# Power.net
KiCad netlist of a schematic drawn in Altium Designer
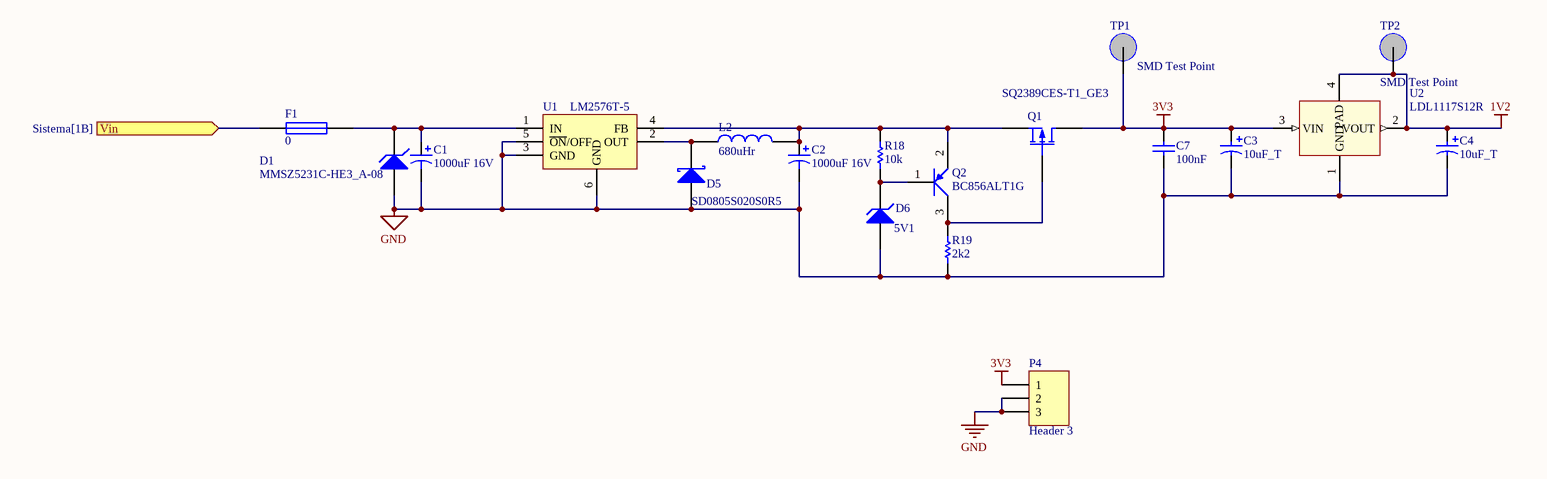
[diagram p0: Power.SchDoc]

(export (version "E")
  (design (tool "Eeschema 10.0.6"))
  (components
    (comp (ref "C1")
      (value "1000uF 16V")
      (footprint "C_SMD_F12")
      (description "Capacitor SMD Elec F12")
      (fields
        (field (name "MANUFACTURER") "KEMET")
        (field (name "MANUFACTURER PART NUMBER") "A768MS108M1CLAE015")
      )
      (libsource (lib "MyLibraryV2") (part "C_1000uF_16V_p"))
    )
    (comp (ref "C2")
      (value "1000uF 16V")
      (footprint "C_SMD_F12")
      (description "Capacitor SMD Elec F12")
      (fields
        (field (name "MANUFACTURER") "KEMET")
        (field (name "MANUFACTURER PART NUMBER") "A768MS108M1CLAE015")
      )
      (libsource (lib "MyLibraryV2") (part "C_1000uF_16V_p"))
    )
    (comp (ref "C3")
      (value "10uF_T")
      (footprint "C_0805_2013_c")
      (description "Capacitor SMD 0805 Tant")
      (fields
        (field (name "MANUFACTURER") "Vishay")
        (field (name "MANUFACTURER PART NUMBER") "TMCP1A106MTRF")
      )
      (libsource (lib "MyLibraryV2") (part "C_10uF_10V_b"))
    )
    (comp (ref "C4")
      (value "10uF_T")
      (footprint "C_0805_2013_c")
      (description "Capacitor SMD 0805 Tant")
      (fields
        (field (name "MANUFACTURER") "Vishay")
        (field (name "MANUFACTURER PART NUMBER") "TMCP1A106MTRF")
      )
      (libsource (lib "MyLibraryV2") (part "C_10uF_10V_b"))
    )
    (comp (ref "C7")
      (value "100nF")
      (footprint "C_0805_2013_b")
      (description "Capacitor SMD 0805")
      (fields (field (name "TOLERANCE") "10%") (field (name "VOLTAGE") "50V"))
      (libsource (lib "MyLibraryV2") (part "C_100nF_50V_b"))
    )
    (comp (ref "D1")
      (value "MMSZ5231C-HE3_A-08")
      (footprint "D_SOD-123")
      (description "Diode SMD SOD-123 Zener 5V1")
      (fields (field (name "TOLERANCE") "2%") (field (name "MANUFACTURER") "Vishay Semiconductors"))
      (libsource (lib "Mi_lib") (part "D_MMSZ5231C-HE3_A-08"))
    )
    (comp (ref "D5")
      (value "SD0805S020S0R5")
      (footprint "D_SOD-123")
      (description "Diode SMD D_SD0805S020S0R5")
      (fields (field (name "MANUFACTURER") "Diodes") (field (name "MANUFACTURER PART NUMBER") "B550C-13-F"))
      (libsource (lib "Mi_lib") (part "D_SD0805S020S0R5"))
    )
    (comp (ref "D6")
      (value "5V1")
      (footprint "D_SOD-123")
      (description "Zener Diode")
      (fields (field (name "TOLERANCE") "3%") (field (name "MANUFACTURER") "Diodes"))
      (libsource (lib "MyLibraryV2") (part "D_DDZ5V1B-7"))
    )
    (comp (ref "F1")
      (value "0")
      (footprint "F_0805_2012")
      (description "(Generico) Fuse SMD 0805")
      (fields (field (name "PUBLISHER") "Altium Limited"))
      (libsource (lib "MyLibraryV2") (part "F_?_0805"))
    )
    (comp (ref "L2")
      (value "680uHr")
      (footprint "L_SMD_10x10")
      (description "(Generico)  Inductor SMD 10x10")
      (libsource (lib "MyLibraryV2") (part "L_?_5"))
    )
    (comp (ref "P4")
      (value "Header 3")
      (footprint "P_HDR1X3_3D")
      (description "Header, 3-Pin")
      (libsource (lib "MyLibraryV2") (part "P_Header 3"))
    )
    (comp (ref "Q1")
      (value "SQ2389CES-T1_GE3")
      (footprint "Q_SOT-23")
      (libsource (lib "Mi_lib") (part "Q_SQ2389CES-T1_GE3"))
    )
    (comp (ref "Q2")
      (value "BC856ALT1G")
      (footprint "Q_SOT-23B_N")
      (description "TRANS PNP 65V 0.1A SOT23")
      (fields (field (name "MANUFACTURER") "ON Semiconductor"))
      (libsource (lib "MyLibraryV2") (part "Q_BC856"))
    )
    (comp (ref "R18")
      (value "10k")
      (footprint "R_0805_2012_a")
      (description "Resistor SMD 0805")
      (fields (field (name "TOLERANCE") "1%") (field (name "MANUFACTURER") "Yageo"))
      (libsource (lib "MyLibraryV2") (part "R_10k_b"))
    )
    (comp (ref "R19")
      (value "2k2")
      (footprint "R_0805_2012_a")
      (description "Resistor SMD 0805")
      (fields (field (name "TOLERANCE") "1%") (field (name "MANUFACTURER") "Bourns"))
      (libsource (lib "MyLibraryV2") (part "R_2k2_b"))
    )
    (comp (ref "TP1")
      (value "SMD Test Point")
      (footprint "TP SMD")
      (description "Test Point SMD")
      (fields (field (name "PUBLISHER") "Altium Limited"))
      (libsource (lib "MyLibraryV2") (part "P_T_TP"))
    )
    (comp (ref "TP2")
      (value "SMD Test Point")
      (footprint "TP SMD")
      (description "Test Point SMD")
      (fields (field (name "PUBLISHER") "Altium Limited"))
      (libsource (lib "MyLibraryV2") (part "P_T_TP"))
    )
    (comp (ref "U1")
      (value "LM2576T-5")
      (footprint "U_SMD_TO-263-5")
      (libsource (lib "MyLibraryV2") (part "U_LM2576-3.3WU"))
    )
    (comp (ref "U2")
      (value "LDL1117S12R")
      (footprint "U_SOT-223")
      (description "LDL1117 Series 1.2 A 2.5 V High PSRR LDO Linear Voltage Regulator-SOT-223")
      (fields
        (field (name "MANUFACTURER") "STMicroelectronics")
        (field (name "MANUFACTURER PART NUMBER") "LDL1117S25R")
      )
      (libsource (lib "MyLibraryV2") (part "U_LDL1117"))
    )
  )
  (nets
    (net (code "1") (name "/Vin") (class "Default")
      (node (ref "F1") (pin "1") (pinfunction "1_1") (pintype "passive"))
    )
    (net (code "2") (name "1V2") (class "Default")
      (node (ref "C4") (pin "1") (pinfunction "1_1") (pintype "passive"))
      (node (ref "TP2") (pin "1") (pinfunction "1_1") (pintype "passive"))
      (node (ref "U2") (pin "2") (pinfunction "VOUT_2") (pintype "output"))
      (node (ref "U2") (pin "4") (pinfunction "PAD_4") (pintype "passive"))
    )
    (net (code "3") (name "3V3") (class "Default")
      (node (ref "C3") (pin "1") (pinfunction "1_1") (pintype "passive"))
      (node (ref "C7") (pin "2") (pinfunction "2_2") (pintype "passive"))
      (node (ref "P4") (pin "1") (pinfunction "1_1") (pintype "passive"))
      (node (ref "Q1") (pin "3") (pinfunction "D_3") (pintype "passive"))
      (node (ref "TP1") (pin "1") (pinfunction "1_1") (pintype "passive"))
      (node (ref "U2") (pin "3") (pinfunction "VIN_3") (pintype "input"))
    )
    (net (code "4") (name "GND") (class "Default")
      (node (ref "C1") (pin "2") (pinfunction "2_2") (pintype "passive"))
      (node (ref "C2") (pin "2") (pinfunction "2_2") (pintype "passive"))
      (node (ref "C3") (pin "2") (pinfunction "2_2") (pintype "passive"))
      (node (ref "C4") (pin "2") (pinfunction "2_2") (pintype "passive"))
      (node (ref "C7") (pin "1") (pinfunction "1_1") (pintype "passive"))
      (node (ref "D1") (pin "2") (pinfunction "A_2") (pintype "passive"))
      (node (ref "D5") (pin "2") (pinfunction "A_2") (pintype "passive"))
      (node (ref "D6") (pin "2") (pinfunction "A_2") (pintype "passive"))
      (node (ref "P4") (pin "2") (pinfunction "2_2") (pintype "passive"))
      (node (ref "P4") (pin "3") (pinfunction "3_3") (pintype "passive"))
      (node (ref "R19") (pin "2") (pinfunction "2_2") (pintype "passive"))
      (node (ref "U1") (pin "3") (pinfunction "GND_3") (pintype "passive"))
      (node (ref "U1") (pin "5") (pinfunction "~{ON}/OFF_5") (pintype "passive"))
      (node (ref "U1") (pin "6") (pinfunction "GND_6") (pintype "passive"))
      (node (ref "U2") (pin "1") (pinfunction "GND_1") (pintype "power_in"))
    )
    (net (code "5") (name "Net-(D1-K)") (class "Default")
      (node (ref "C1") (pin "1") (pinfunction "1_1") (pintype "passive"))
      (node (ref "D1") (pin "1") (pinfunction "K_1") (pintype "passive"))
      (node (ref "F1") (pin "2") (pinfunction "2_2") (pintype "passive"))
      (node (ref "U1") (pin "1") (pinfunction "IN_1") (pintype "passive"))
    )
    (net (code "6") (name "Net-(D5-K)") (class "Default")
      (node (ref "D5") (pin "1") (pinfunction "K_1") (pintype "passive"))
      (node (ref "L2") (pin "1") (pinfunction "1_1") (pintype "passive"))
      (node (ref "U1") (pin "2") (pinfunction "OUT_2") (pintype "passive"))
    )
    (net (code "7") (name "Net-(D6-K)") (class "Default")
      (node (ref "D6") (pin "1") (pinfunction "K_1") (pintype "passive"))
      (node (ref "Q2") (pin "1") (pinfunction "B_1") (pintype "passive"))
      (node (ref "R18") (pin "1") (pinfunction "1_1") (pintype "passive"))
    )
    (net (code "8") (name "Net-(Q1-G)") (class "Default")
      (node (ref "Q1") (pin "1") (pinfunction "G_1") (pintype "passive"))
      (node (ref "Q2") (pin "3") (pinfunction "C_3") (pintype "passive"))
      (node (ref "R19") (pin "1") (pinfunction "1_1") (pintype "passive"))
    )
    (net (code "9") (name "Net-(Q1-S)") (class "Default")
      (node (ref "C2") (pin "1") (pinfunction "1_1") (pintype "passive"))
      (node (ref "L2") (pin "2") (pinfunction "2_2") (pintype "passive"))
      (node (ref "Q1") (pin "2") (pinfunction "S_2") (pintype "passive"))
      (node (ref "Q2") (pin "2") (pinfunction "E_2") (pintype "passive"))
      (node (ref "R18") (pin "2") (pinfunction "2_2") (pintype "passive"))
      (node (ref "U1") (pin "4") (pinfunction "FB_4") (pintype "passive"))
    )
  )
)
